# SCH_easyeda.net
KiCad netlist of a schematic drawn in EasyEDA
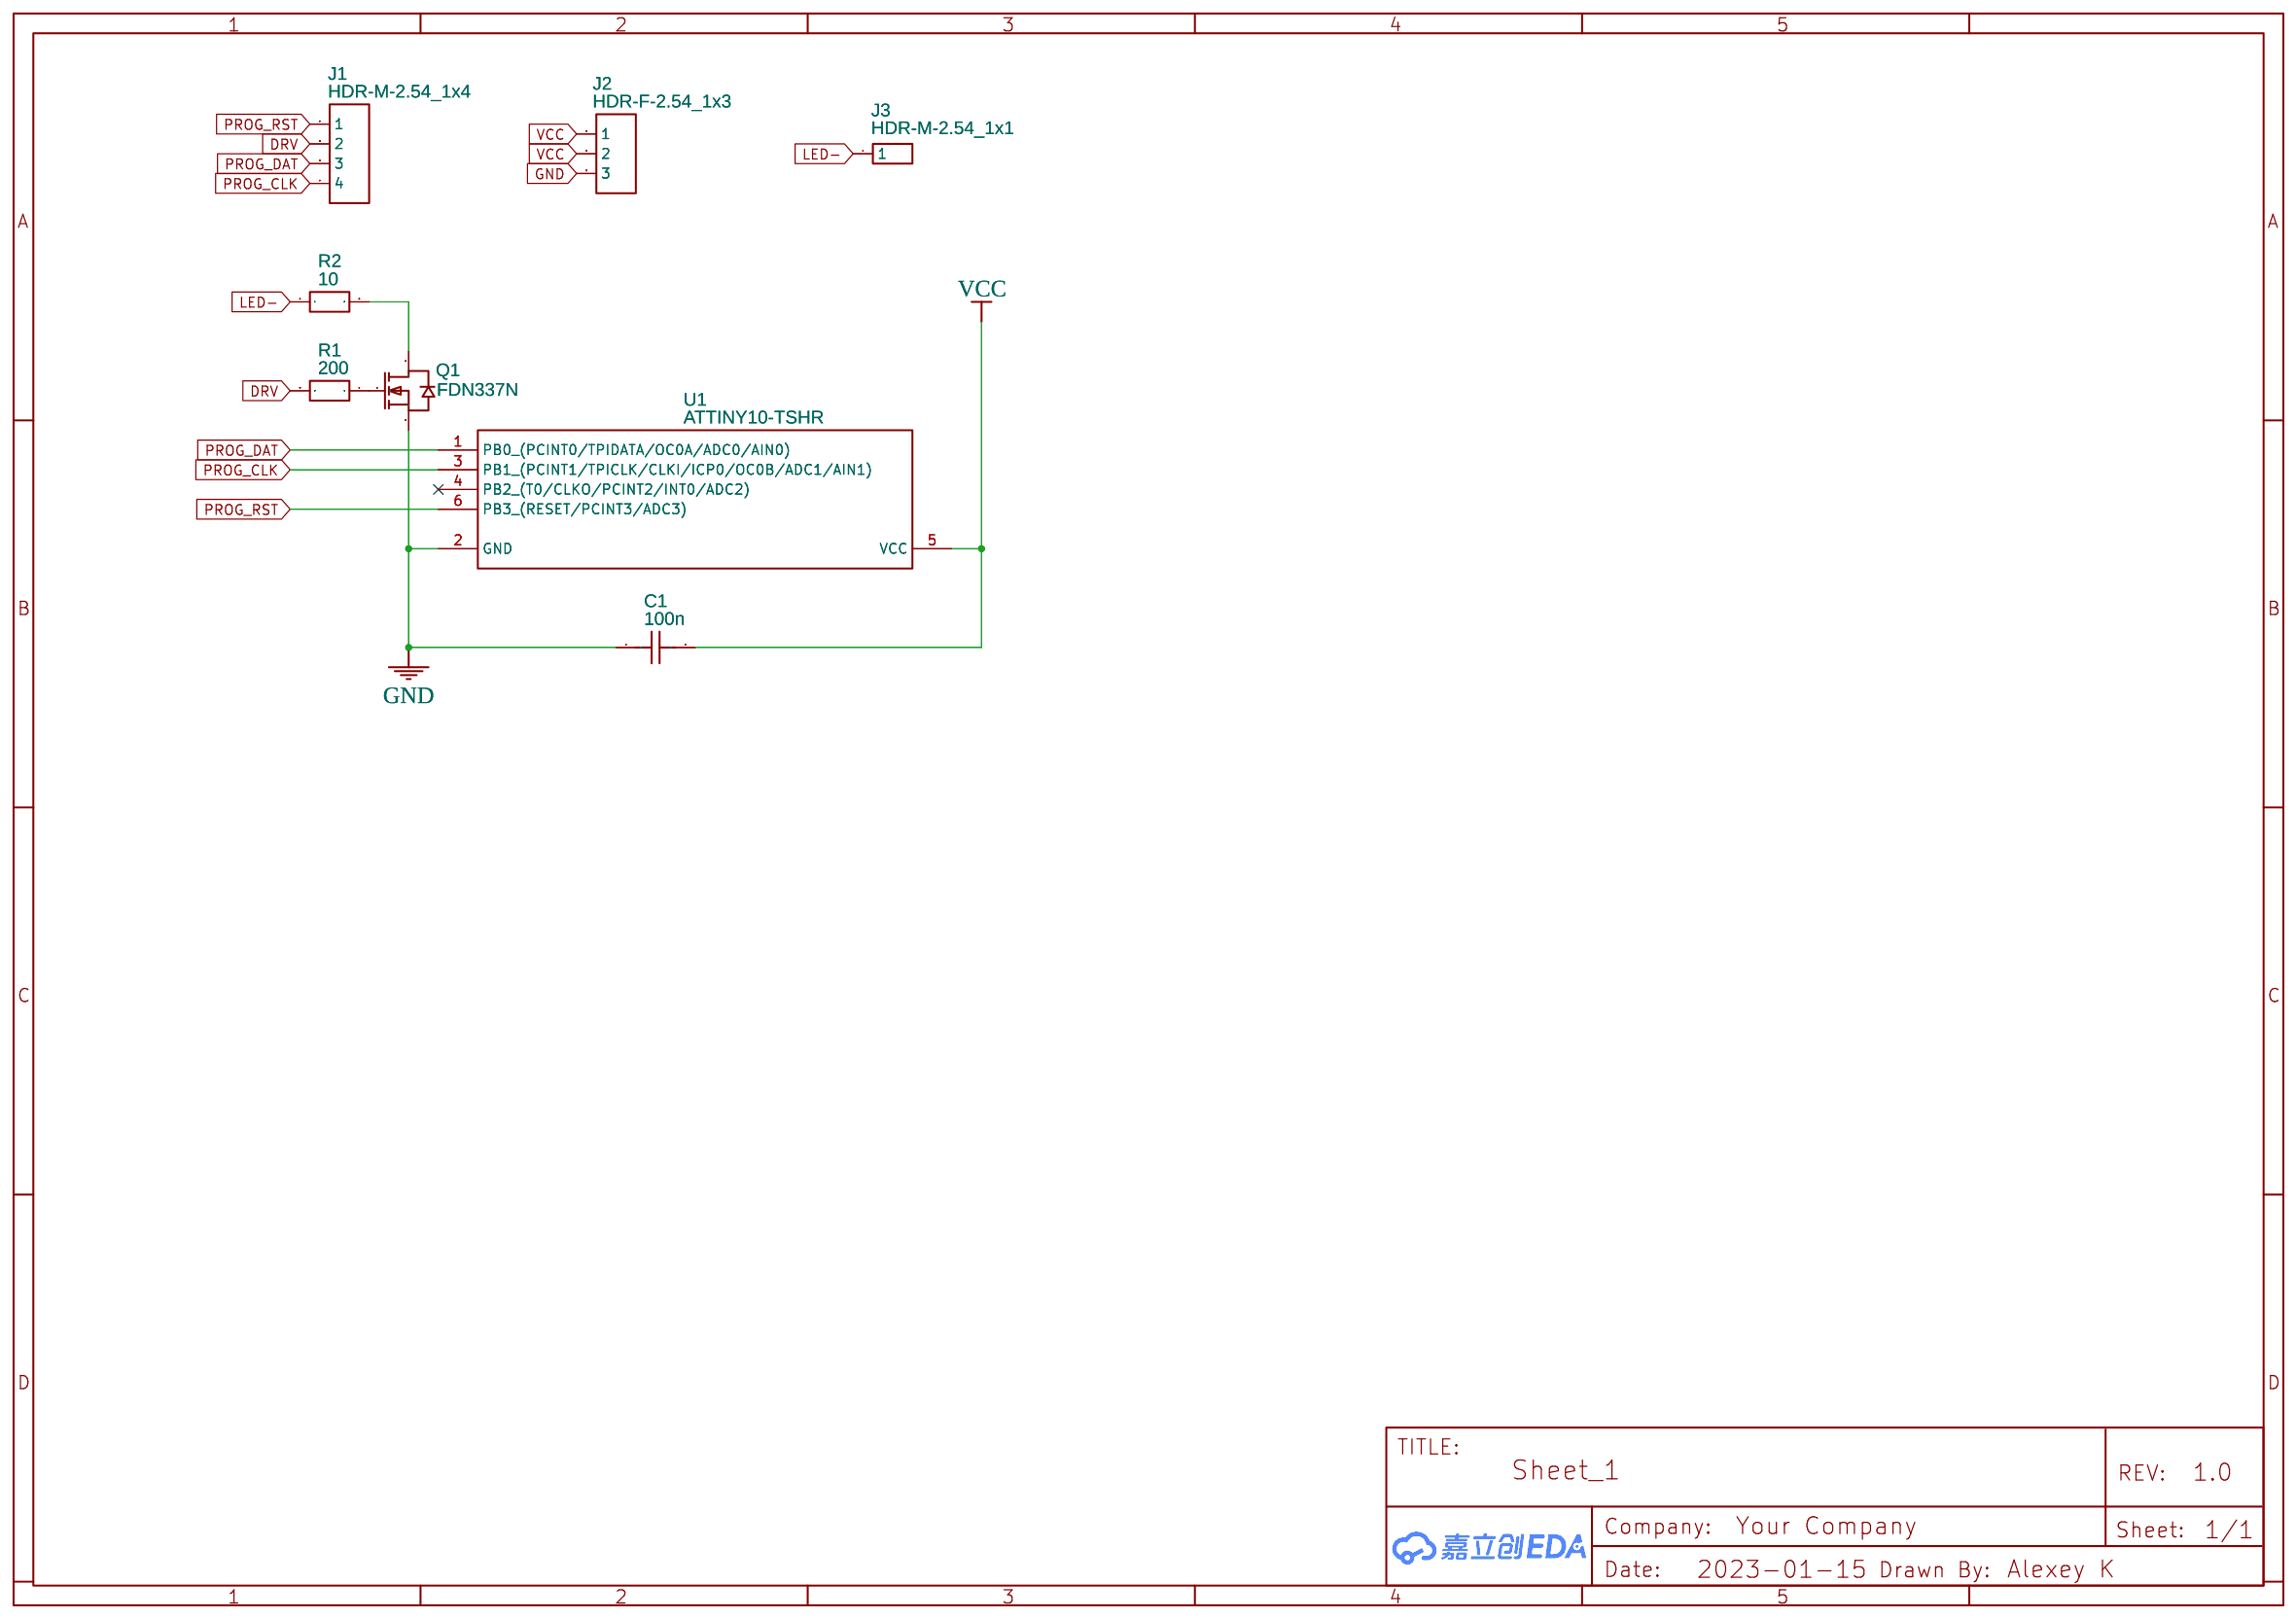
[diagram p0: schematic sheet]

(export (version "E")
  (design (tool "Eeschema 10.0.6"))
  (components
    (comp (ref "C1") (value "100n") (libsource (lib "") (part "C_0805_US")))
    (comp (ref "J1") (value "HDR-M-2.54_1x4") (libsource (lib "") (part "HDR-M-2.54_1x4")))
    (comp (ref "J2") (value "HDR-F-2.54_1x3") (libsource (lib "") (part "HDR-F-2.54_1x3")))
    (comp (ref "J3") (value "HDR-M-2.54_1x1") (libsource (lib "") (part "HDR-M-2.54_1x1")))
    (comp (ref "Q1")
      (value "FDN337N")
      (fields (field (name "Manufacturer") "TECH PUBLIC(台舟)"))
      (libsource (lib "") (part "FDN337N_C5182040"))
    )
    (comp (ref "R1") (value "200") (libsource (lib "") (part "R_0805_EU")))
    (comp (ref "R2") (value "10") (libsource (lib "") (part "R_0805_EU_1")))
    (comp (ref "U1")
      (value "ATTINY10-TSHR")
      (fields (field (name "Manufacturer") "MICROCHIP(美国微芯)"))
      (libsource (lib "") (part "ATTINY10-TSHR"))
    )
  )
  (nets
    (net (code "1") (name "DRV") (class "Default")
      (node (ref "J1") (pin "2") (pinfunction "2_2") (pintype "unspecified"))
      (node (ref "R1") (pin "2") (pinfunction "2_2") (pintype "unspecified"))
    )
    (net (code "2") (name "GND") (class "Default")
      (node (ref "C1") (pin "1") (pinfunction "1_1") (pintype "unspecified"))
      (node (ref "J2") (pin "3") (pinfunction "3_3") (pintype "input"))
      (node (ref "Q1") (pin "2") (pinfunction "S_2") (pintype "unspecified"))
      (node (ref "U1") (pin "2") (pinfunction "GND_2") (pintype "passive"))
    )
    (net (code "3") (name "LED-") (class "Default")
      (node (ref "J3") (pin "1") (pinfunction "1_1") (pintype "input"))
      (node (ref "R2") (pin "1") (pinfunction "1_1") (pintype "unspecified"))
    )
    (net (code "4") (name "Net-(Q1-D)") (class "Default")
      (node (ref "Q1") (pin "3") (pinfunction "D_3") (pintype "unspecified"))
      (node (ref "R2") (pin "2") (pinfunction "2_2") (pintype "unspecified"))
    )
    (net (code "5") (name "Net-(Q1-G)") (class "Default")
      (node (ref "Q1") (pin "1") (pinfunction "G_1") (pintype "unspecified"))
      (node (ref "R1") (pin "1") (pinfunction "1_1") (pintype "unspecified"))
    )
    (net (code "6") (name "PROG_CLK") (class "Default")
      (node (ref "J1") (pin "4") (pinfunction "4_4") (pintype "unspecified"))
      (node (ref "U1") (pin "3") (pinfunction "PB1_(PCINT1/TPICLK/CLKI/ICP0/OC0B/ADC1/AIN1)_3") (pintype "bidirectional"))
    )
    (net (code "7") (name "PROG_DAT") (class "Default")
      (node (ref "J1") (pin "3") (pinfunction "3_3") (pintype "unspecified"))
      (node (ref "U1") (pin "1") (pinfunction "PB0_(PCINT0/TPIDATA/OC0A/ADC0/AIN0)_1") (pintype "bidirectional"))
    )
    (net (code "8") (name "PROG_RST") (class "Default")
      (node (ref "J1") (pin "1") (pinfunction "1_1") (pintype "unspecified"))
      (node (ref "U1") (pin "6") (pinfunction "PB3_(RESET/PCINT3/ADC3)_6") (pintype "bidirectional"))
    )
    (net (code "9") (name "VCC") (class "Default")
      (node (ref "C1") (pin "2") (pinfunction "2_2") (pintype "unspecified"))
      (node (ref "J2") (pin "1") (pinfunction "1_1") (pintype "input"))
      (node (ref "J2") (pin "2") (pinfunction "2_2") (pintype "input"))
      (node (ref "U1") (pin "5") (pinfunction "VCC_5") (pintype "passive"))
    )
    (net (code "10") (name "unconnected-(U1-PB2_(T0{slash}CLKO{slash}PCINT2{slash}INT0{slash}ADC2)-Pad4)") (class "Default")
      (node (ref "U1") (pin "4") (pinfunction "PB2_(T0/CLKO/PCINT2/INT0/ADC2)_4") (pintype "bidirectional+no_connect"))
    )
  )
)
